# microcontroller.net
KiCad netlist of a schematic drawn in Altium Designer
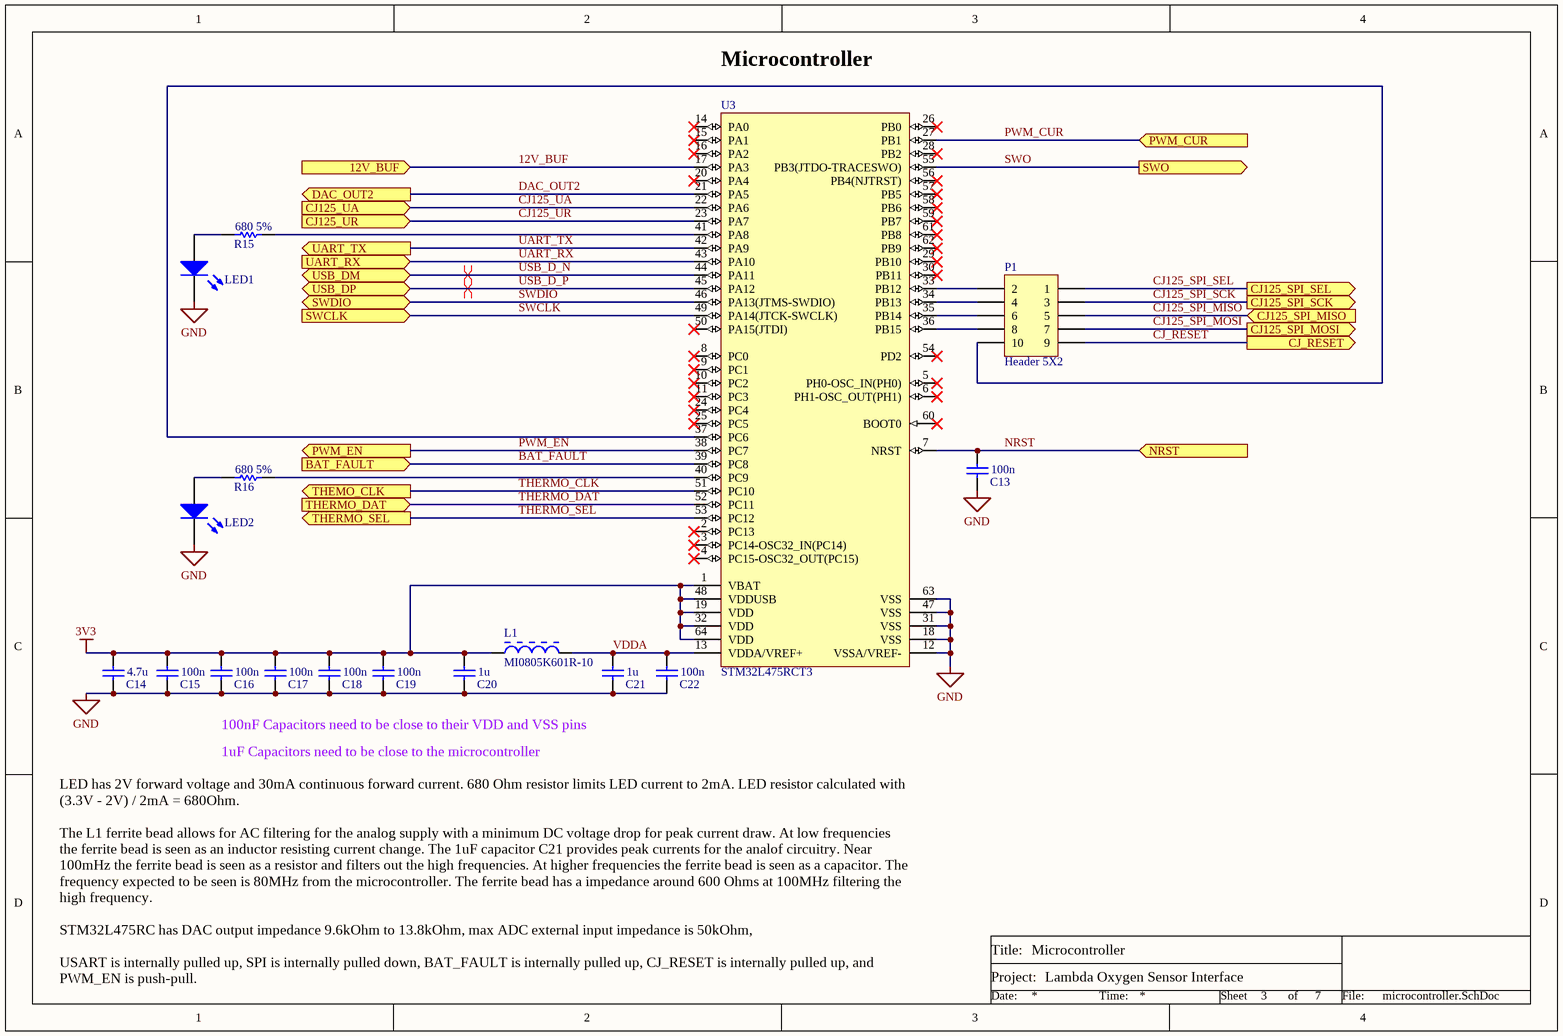
[diagram p0: microcontroller.SchDoc]

(export (version "E")
  (design (tool "Eeschema 10.0.6"))
  (components
    (comp (ref "C13")
      (value "100n")
      (footprint "0805")
      (description "Generic 0805 Capacitor")
      (libsource (lib "symbol_library") (part "C_0805"))
    )
    (comp (ref "C14")
      (value "4.7u")
      (footprint "1206")
      (description "Generic 1206 Capacitor")
      (libsource (lib "symbol_library") (part "C_1206"))
    )
    (comp (ref "C15")
      (value "100n")
      (footprint "0805")
      (description "Generic 0805 Capacitor")
      (libsource (lib "symbol_library") (part "C_0805"))
    )
    (comp (ref "C16")
      (value "100n")
      (footprint "0805")
      (description "Generic 0805 Capacitor")
      (libsource (lib "symbol_library") (part "C_0805"))
    )
    (comp (ref "C17")
      (value "100n")
      (footprint "0805")
      (description "Generic 0805 Capacitor")
      (libsource (lib "symbol_library") (part "C_0805"))
    )
    (comp (ref "C18")
      (value "100n")
      (footprint "0805")
      (description "Generic 0805 Capacitor")
      (libsource (lib "symbol_library") (part "C_0805"))
    )
    (comp (ref "C19")
      (value "100n")
      (footprint "0805")
      (description "Generic 0805 Capacitor")
      (libsource (lib "symbol_library") (part "C_0805"))
    )
    (comp (ref "C20")
      (value "1u")
      (footprint "1206")
      (description "Generic 1206 Capacitor")
      (libsource (lib "symbol_library") (part "C_1206"))
    )
    (comp (ref "C21")
      (value "1u")
      (footprint "1206")
      (description "Generic 1206 Capacitor")
      (libsource (lib "symbol_library") (part "C_1206"))
    )
    (comp (ref "C22")
      (value "100n")
      (footprint "0805")
      (description "Generic 0805 Capacitor")
      (libsource (lib "symbol_library") (part "C_0805"))
    )
    (comp (ref "L1")
      (value "MI0805K601R-10")
      (footprint "0805")
      (fields (field (name "MANUFACTURER") "Laird"))
      (libsource (lib "symbol_library") (part "MI0805K"))
    )
    (comp (ref "LED1")
      (value "150080SS75000")
      (footprint "0805_A")
      (description "SMD mono-color Chip LED, WL-SMCW, Super Red")
      (fields (field (name "MANUFACTURER") "Wuerth Elektronik"))
      (libsource (lib "symbol_library") (part "LED_0805"))
    )
    (comp (ref "LED2")
      (value "150080SS75000")
      (footprint "0805_A")
      (description "SMD mono-color Chip LED, WL-SMCW, Super Red")
      (fields (field (name "MANUFACTURER") "Wuerth Elektronik"))
      (libsource (lib "symbol_library") (part "LED_0805"))
    )
    (comp (ref "P1")
      (value "Header 5X2")
      (footprint "HDR2X5")
      (description "Header, 5-Pin, Dual row")
      (fields (field (name "PUBLISHER") "Altium Limited"))
      (libsource (lib "Miscellaneous Connectors") (part "Header 5X2"))
    )
    (comp (ref "R15")
      (value "680 5%")
      (footprint "0603")
      (description "Generic 0603 Resistor")
      (libsource (lib "symbol_library") (part "R_0603"))
    )
    (comp (ref "R16")
      (value "680 5%")
      (footprint "0603")
      (description "Generic 0603 Resistor")
      (libsource (lib "symbol_library") (part "R_0603"))
    )
    (comp (ref "U3")
      (value "STM32L475RCT3")
      (footprint "STM-LQFP64_L")
      (libsource (lib "symbol_library") (part "STM32L475RCT3"))
    )
  )
  (nets
    (net (code "1") (name "/12V_BUF") (class "Default")
      (node (ref "U3") (pin "17") (pinfunction "PA3_17") (pintype "bidirectional"))
    )
    (net (code "2") (name "/BAT_FAULT") (class "Default")
      (node (ref "U3") (pin "39") (pinfunction "PC8_39") (pintype "bidirectional"))
    )
    (net (code "3") (name "/CJ125_SPI_MISO") (class "Default")
      (node (ref "P1") (pin "5") (pinfunction "5_5") (pintype "passive"))
    )
    (net (code "4") (name "/CJ125_SPI_MOSI") (class "Default")
      (node (ref "P1") (pin "7") (pinfunction "7_7") (pintype "passive"))
    )
    (net (code "5") (name "/CJ125_SPI_SCK") (class "Default")
      (node (ref "P1") (pin "3") (pinfunction "3_3") (pintype "passive"))
    )
    (net (code "6") (name "/CJ125_SPI_SEL") (class "Default")
      (node (ref "P1") (pin "1") (pinfunction "1_1") (pintype "passive"))
    )
    (net (code "7") (name "/CJ125_UA") (class "Default")
      (node (ref "U3") (pin "22") (pinfunction "PA6_22") (pintype "bidirectional"))
    )
    (net (code "8") (name "/CJ125_UR") (class "Default")
      (node (ref "U3") (pin "23") (pinfunction "PA7_23") (pintype "bidirectional"))
    )
    (net (code "9") (name "/CJ_RESET") (class "Default")
      (node (ref "P1") (pin "9") (pinfunction "9_9") (pintype "passive"))
    )
    (net (code "10") (name "/DAC_OUT2") (class "Default")
      (node (ref "U3") (pin "21") (pinfunction "PA5_21") (pintype "bidirectional"))
    )
    (net (code "11") (name "/NRST") (class "Default")
      (node (ref "C13") (pin "2") (pinfunction "2_2") (pintype "passive"))
      (node (ref "U3") (pin "7") (pinfunction "NRST_7") (pintype "bidirectional"))
    )
    (net (code "12") (name "/PWM_CUR") (class "Default")
      (node (ref "U3") (pin "27") (pinfunction "PB1_27") (pintype "bidirectional"))
    )
    (net (code "13") (name "/PWM_EN") (class "Default")
      (node (ref "U3") (pin "38") (pinfunction "PC7_38") (pintype "bidirectional"))
    )
    (net (code "14") (name "/SWCLK") (class "Default")
      (node (ref "U3") (pin "49") (pinfunction "PA14(JTCK-SWCLK)_49") (pintype "bidirectional"))
    )
    (net (code "15") (name "/SWDIO") (class "Default")
      (node (ref "U3") (pin "46") (pinfunction "PA13(JTMS-SWDIO)_46") (pintype "bidirectional"))
    )
    (net (code "16") (name "/SWO") (class "Default")
      (node (ref "U3") (pin "55") (pinfunction "PB3(JTDO-TRACESWO)_55") (pintype "bidirectional"))
    )
    (net (code "17") (name "/THERMO_CLK") (class "Default")
      (node (ref "U3") (pin "51") (pinfunction "PC10_51") (pintype "bidirectional"))
    )
    (net (code "18") (name "/THERMO_DAT") (class "Default")
      (node (ref "U3") (pin "52") (pinfunction "PC11_52") (pintype "bidirectional"))
    )
    (net (code "19") (name "/THERMO_SEL") (class "Default")
      (node (ref "U3") (pin "53") (pinfunction "PC12_53") (pintype "bidirectional"))
    )
    (net (code "20") (name "/UART_RX") (class "Default")
      (node (ref "U3") (pin "43") (pinfunction "PA10_43") (pintype "bidirectional"))
    )
    (net (code "21") (name "/UART_TX") (class "Default")
      (node (ref "U3") (pin "42") (pinfunction "PA9_42") (pintype "bidirectional"))
    )
    (net (code "22") (name "/USB_D_N") (class "Default")
      (node (ref "U3") (pin "44") (pinfunction "PA11_44") (pintype "bidirectional"))
    )
    (net (code "23") (name "/USB_D_P") (class "Default")
      (node (ref "U3") (pin "45") (pinfunction "PA12_45") (pintype "bidirectional"))
    )
    (net (code "24") (name "/VDDA") (class "Default")
      (node (ref "C21") (pin "2") (pinfunction "2_2") (pintype "passive"))
      (node (ref "C22") (pin "2") (pinfunction "2_2") (pintype "passive"))
      (node (ref "L1") (pin "2") (pinfunction "2_2") (pintype "passive"))
      (node (ref "U3") (pin "13") (pinfunction "VDDA/VREF+_13") (pintype "power_in"))
    )
    (net (code "25") (name "3V3") (class "Default")
      (node (ref "C14") (pin "2") (pinfunction "2_2") (pintype "passive"))
      (node (ref "C15") (pin "2") (pinfunction "2_2") (pintype "passive"))
      (node (ref "C16") (pin "2") (pinfunction "2_2") (pintype "passive"))
      (node (ref "C17") (pin "2") (pinfunction "2_2") (pintype "passive"))
      (node (ref "C18") (pin "2") (pinfunction "2_2") (pintype "passive"))
      (node (ref "C19") (pin "2") (pinfunction "2_2") (pintype "passive"))
      (node (ref "C20") (pin "2") (pinfunction "2_2") (pintype "passive"))
      (node (ref "L1") (pin "1") (pinfunction "1_1") (pintype "passive"))
      (node (ref "U3") (pin "1") (pinfunction "VBAT_1") (pintype "power_in"))
      (node (ref "U3") (pin "19") (pinfunction "VDD_19") (pintype "power_in"))
      (node (ref "U3") (pin "32") (pinfunction "VDD_32") (pintype "power_in"))
      (node (ref "U3") (pin "48") (pinfunction "VDDUSB_48") (pintype "power_in"))
      (node (ref "U3") (pin "64") (pinfunction "VDD_64") (pintype "power_in"))
    )
    (net (code "26") (name "GND") (class "Default")
      (node (ref "C13") (pin "1") (pinfunction "1_1") (pintype "passive"))
      (node (ref "C14") (pin "1") (pinfunction "1_1") (pintype "passive"))
      (node (ref "C15") (pin "1") (pinfunction "1_1") (pintype "passive"))
      (node (ref "C16") (pin "1") (pinfunction "1_1") (pintype "passive"))
      (node (ref "C17") (pin "1") (pinfunction "1_1") (pintype "passive"))
      (node (ref "C18") (pin "1") (pinfunction "1_1") (pintype "passive"))
      (node (ref "C19") (pin "1") (pinfunction "1_1") (pintype "passive"))
      (node (ref "C20") (pin "1") (pinfunction "1_1") (pintype "passive"))
      (node (ref "C21") (pin "1") (pinfunction "1_1") (pintype "passive"))
      (node (ref "C22") (pin "1") (pinfunction "1_1") (pintype "passive"))
      (node (ref "LED1") (pin "1") (pinfunction "K_1") (pintype "passive"))
      (node (ref "LED2") (pin "1") (pinfunction "K_1") (pintype "passive"))
      (node (ref "U3") (pin "12") (pinfunction "VSSA/VREF-_12") (pintype "power_in"))
      (node (ref "U3") (pin "18") (pinfunction "VSS_18") (pintype "power_in"))
      (node (ref "U3") (pin "31") (pinfunction "VSS_31") (pintype "power_in"))
      (node (ref "U3") (pin "47") (pinfunction "VSS_47") (pintype "power_in"))
      (node (ref "U3") (pin "63") (pinfunction "VSS_63") (pintype "power_in"))
    )
    (net (code "27") (name "Net-(LED1-A)") (class "Default")
      (node (ref "LED1") (pin "2") (pinfunction "A_2") (pintype "passive"))
      (node (ref "R15") (pin "1") (pinfunction "1_1") (pintype "passive"))
    )
    (net (code "28") (name "Net-(LED2-A)") (class "Default")
      (node (ref "LED2") (pin "2") (pinfunction "A_2") (pintype "passive"))
      (node (ref "R16") (pin "1") (pinfunction "1_1") (pintype "passive"))
    )
    (net (code "29") (name "Net-(U3-PA8)") (class "Default")
      (node (ref "R15") (pin "2") (pinfunction "2_2") (pintype "passive"))
      (node (ref "U3") (pin "41") (pinfunction "PA8_41") (pintype "bidirectional"))
    )
    (net (code "30") (name "Net-(U3-PB12)") (class "Default")
      (node (ref "P1") (pin "2") (pinfunction "2_2") (pintype "passive"))
      (node (ref "U3") (pin "33") (pinfunction "PB12_33") (pintype "bidirectional"))
    )
    (net (code "31") (name "Net-(U3-PB13)") (class "Default")
      (node (ref "P1") (pin "4") (pinfunction "4_4") (pintype "passive"))
      (node (ref "U3") (pin "34") (pinfunction "PB13_34") (pintype "bidirectional"))
    )
    (net (code "32") (name "Net-(U3-PB14)") (class "Default")
      (node (ref "P1") (pin "6") (pinfunction "6_6") (pintype "passive"))
      (node (ref "U3") (pin "35") (pinfunction "PB14_35") (pintype "bidirectional"))
    )
    (net (code "33") (name "Net-(U3-PB15)") (class "Default")
      (node (ref "P1") (pin "8") (pinfunction "8_8") (pintype "passive"))
      (node (ref "U3") (pin "36") (pinfunction "PB15_36") (pintype "bidirectional"))
    )
    (net (code "34") (name "Net-(U3-PC6)") (class "Default")
      (node (ref "P1") (pin "10") (pinfunction "10_10") (pintype "passive"))
      (node (ref "U3") (pin "37") (pinfunction "PC6_37") (pintype "bidirectional"))
    )
    (net (code "35") (name "Net-(U3-PC9)") (class "Default")
      (node (ref "R16") (pin "2") (pinfunction "2_2") (pintype "passive"))
      (node (ref "U3") (pin "40") (pinfunction "PC9_40") (pintype "bidirectional"))
    )
    (net (code "36") (name "unconnected-(U3-BOOT0-Pad60)") (class "Default")
      (node (ref "U3") (pin "60") (pinfunction "BOOT0_60") (pintype "input+no_connect"))
    )
    (net (code "37") (name "unconnected-(U3-PA0-Pad14)") (class "Default")
      (node (ref "U3") (pin "14") (pinfunction "PA0_14") (pintype "bidirectional+no_connect"))
    )
    (net (code "38") (name "unconnected-(U3-PA1-Pad15)") (class "Default")
      (node (ref "U3") (pin "15") (pinfunction "PA1_15") (pintype "bidirectional+no_connect"))
    )
    (net (code "39") (name "unconnected-(U3-PA2-Pad16)") (class "Default")
      (node (ref "U3") (pin "16") (pinfunction "PA2_16") (pintype "bidirectional+no_connect"))
    )
    (net (code "40") (name "unconnected-(U3-PA4-Pad20)") (class "Default")
      (node (ref "U3") (pin "20") (pinfunction "PA4_20") (pintype "bidirectional+no_connect"))
    )
    (net (code "41") (name "unconnected-(U3-PA15(JTDI)-Pad50)") (class "Default")
      (node (ref "U3") (pin "50") (pinfunction "PA15(JTDI)_50") (pintype "bidirectional+no_connect"))
    )
    (net (code "42") (name "unconnected-(U3-PB0-Pad26)") (class "Default")
      (node (ref "U3") (pin "26") (pinfunction "PB0_26") (pintype "bidirectional+no_connect"))
    )
    (net (code "43") (name "unconnected-(U3-PB2-Pad28)") (class "Default")
      (node (ref "U3") (pin "28") (pinfunction "PB2_28") (pintype "bidirectional+no_connect"))
    )
    (net (code "44") (name "unconnected-(U3-PB4(NJTRST)-Pad56)") (class "Default")
      (node (ref "U3") (pin "56") (pinfunction "PB4(NJTRST)_56") (pintype "bidirectional+no_connect"))
    )
    (net (code "45") (name "unconnected-(U3-PB5-Pad57)") (class "Default")
      (node (ref "U3") (pin "57") (pinfunction "PB5_57") (pintype "bidirectional+no_connect"))
    )
    (net (code "46") (name "unconnected-(U3-PB6-Pad58)") (class "Default")
      (node (ref "U3") (pin "58") (pinfunction "PB6_58") (pintype "bidirectional+no_connect"))
    )
    (net (code "47") (name "unconnected-(U3-PB7-Pad59)") (class "Default")
      (node (ref "U3") (pin "59") (pinfunction "PB7_59") (pintype "bidirectional+no_connect"))
    )
    (net (code "48") (name "unconnected-(U3-PB8-Pad61)") (class "Default")
      (node (ref "U3") (pin "61") (pinfunction "PB8_61") (pintype "bidirectional+no_connect"))
    )
    (net (code "49") (name "unconnected-(U3-PB9-Pad62)") (class "Default")
      (node (ref "U3") (pin "62") (pinfunction "PB9_62") (pintype "bidirectional+no_connect"))
    )
    (net (code "50") (name "unconnected-(U3-PB10-Pad29)") (class "Default")
      (node (ref "U3") (pin "29") (pinfunction "PB10_29") (pintype "bidirectional+no_connect"))
    )
    (net (code "51") (name "unconnected-(U3-PB11-Pad30)") (class "Default")
      (node (ref "U3") (pin "30") (pinfunction "PB11_30") (pintype "bidirectional+no_connect"))
    )
    (net (code "52") (name "unconnected-(U3-PC0-Pad8)") (class "Default")
      (node (ref "U3") (pin "8") (pinfunction "PC0_8") (pintype "bidirectional+no_connect"))
    )
    (net (code "53") (name "unconnected-(U3-PC1-Pad9)") (class "Default")
      (node (ref "U3") (pin "9") (pinfunction "PC1_9") (pintype "bidirectional+no_connect"))
    )
    (net (code "54") (name "unconnected-(U3-PC2-Pad10)") (class "Default")
      (node (ref "U3") (pin "10") (pinfunction "PC2_10") (pintype "bidirectional+no_connect"))
    )
    (net (code "55") (name "unconnected-(U3-PC3-Pad11)") (class "Default")
      (node (ref "U3") (pin "11") (pinfunction "PC3_11") (pintype "bidirectional+no_connect"))
    )
    (net (code "56") (name "unconnected-(U3-PC4-Pad24)") (class "Default")
      (node (ref "U3") (pin "24") (pinfunction "PC4_24") (pintype "bidirectional+no_connect"))
    )
    (net (code "57") (name "unconnected-(U3-PC5-Pad25)") (class "Default")
      (node (ref "U3") (pin "25") (pinfunction "PC5_25") (pintype "bidirectional+no_connect"))
    )
    (net (code "58") (name "unconnected-(U3-PC13-Pad2)") (class "Default")
      (node (ref "U3") (pin "2") (pinfunction "PC13_2") (pintype "bidirectional+no_connect"))
    )
    (net (code "59") (name "unconnected-(U3-PC14-OSC32_IN(PC14)-Pad3)") (class "Default")
      (node (ref "U3") (pin "3") (pinfunction "PC14-OSC32_IN(PC14)_3") (pintype "bidirectional+no_connect"))
    )
    (net (code "60") (name "unconnected-(U3-PC15-OSC32_OUT(PC15)-Pad4)") (class "Default")
      (node (ref "U3") (pin "4") (pinfunction "PC15-OSC32_OUT(PC15)_4") (pintype "bidirectional+no_connect"))
    )
    (net (code "61") (name "unconnected-(U3-PD2-Pad54)") (class "Default")
      (node (ref "U3") (pin "54") (pinfunction "PD2_54") (pintype "bidirectional+no_connect"))
    )
    (net (code "62") (name "unconnected-(U3-PH0-OSC_IN(PH0)-Pad5)") (class "Default")
      (node (ref "U3") (pin "5") (pinfunction "PH0-OSC_IN(PH0)_5") (pintype "bidirectional+no_connect"))
    )
    (net (code "63") (name "unconnected-(U3-PH1-OSC_OUT(PH1)-Pad6)") (class "Default")
      (node (ref "U3") (pin "6") (pinfunction "PH1-OSC_OUT(PH1)_6") (pintype "bidirectional+no_connect"))
    )
  )
)
